# Motores.net
KiCad netlist of a schematic drawn in EasyEDA Pro
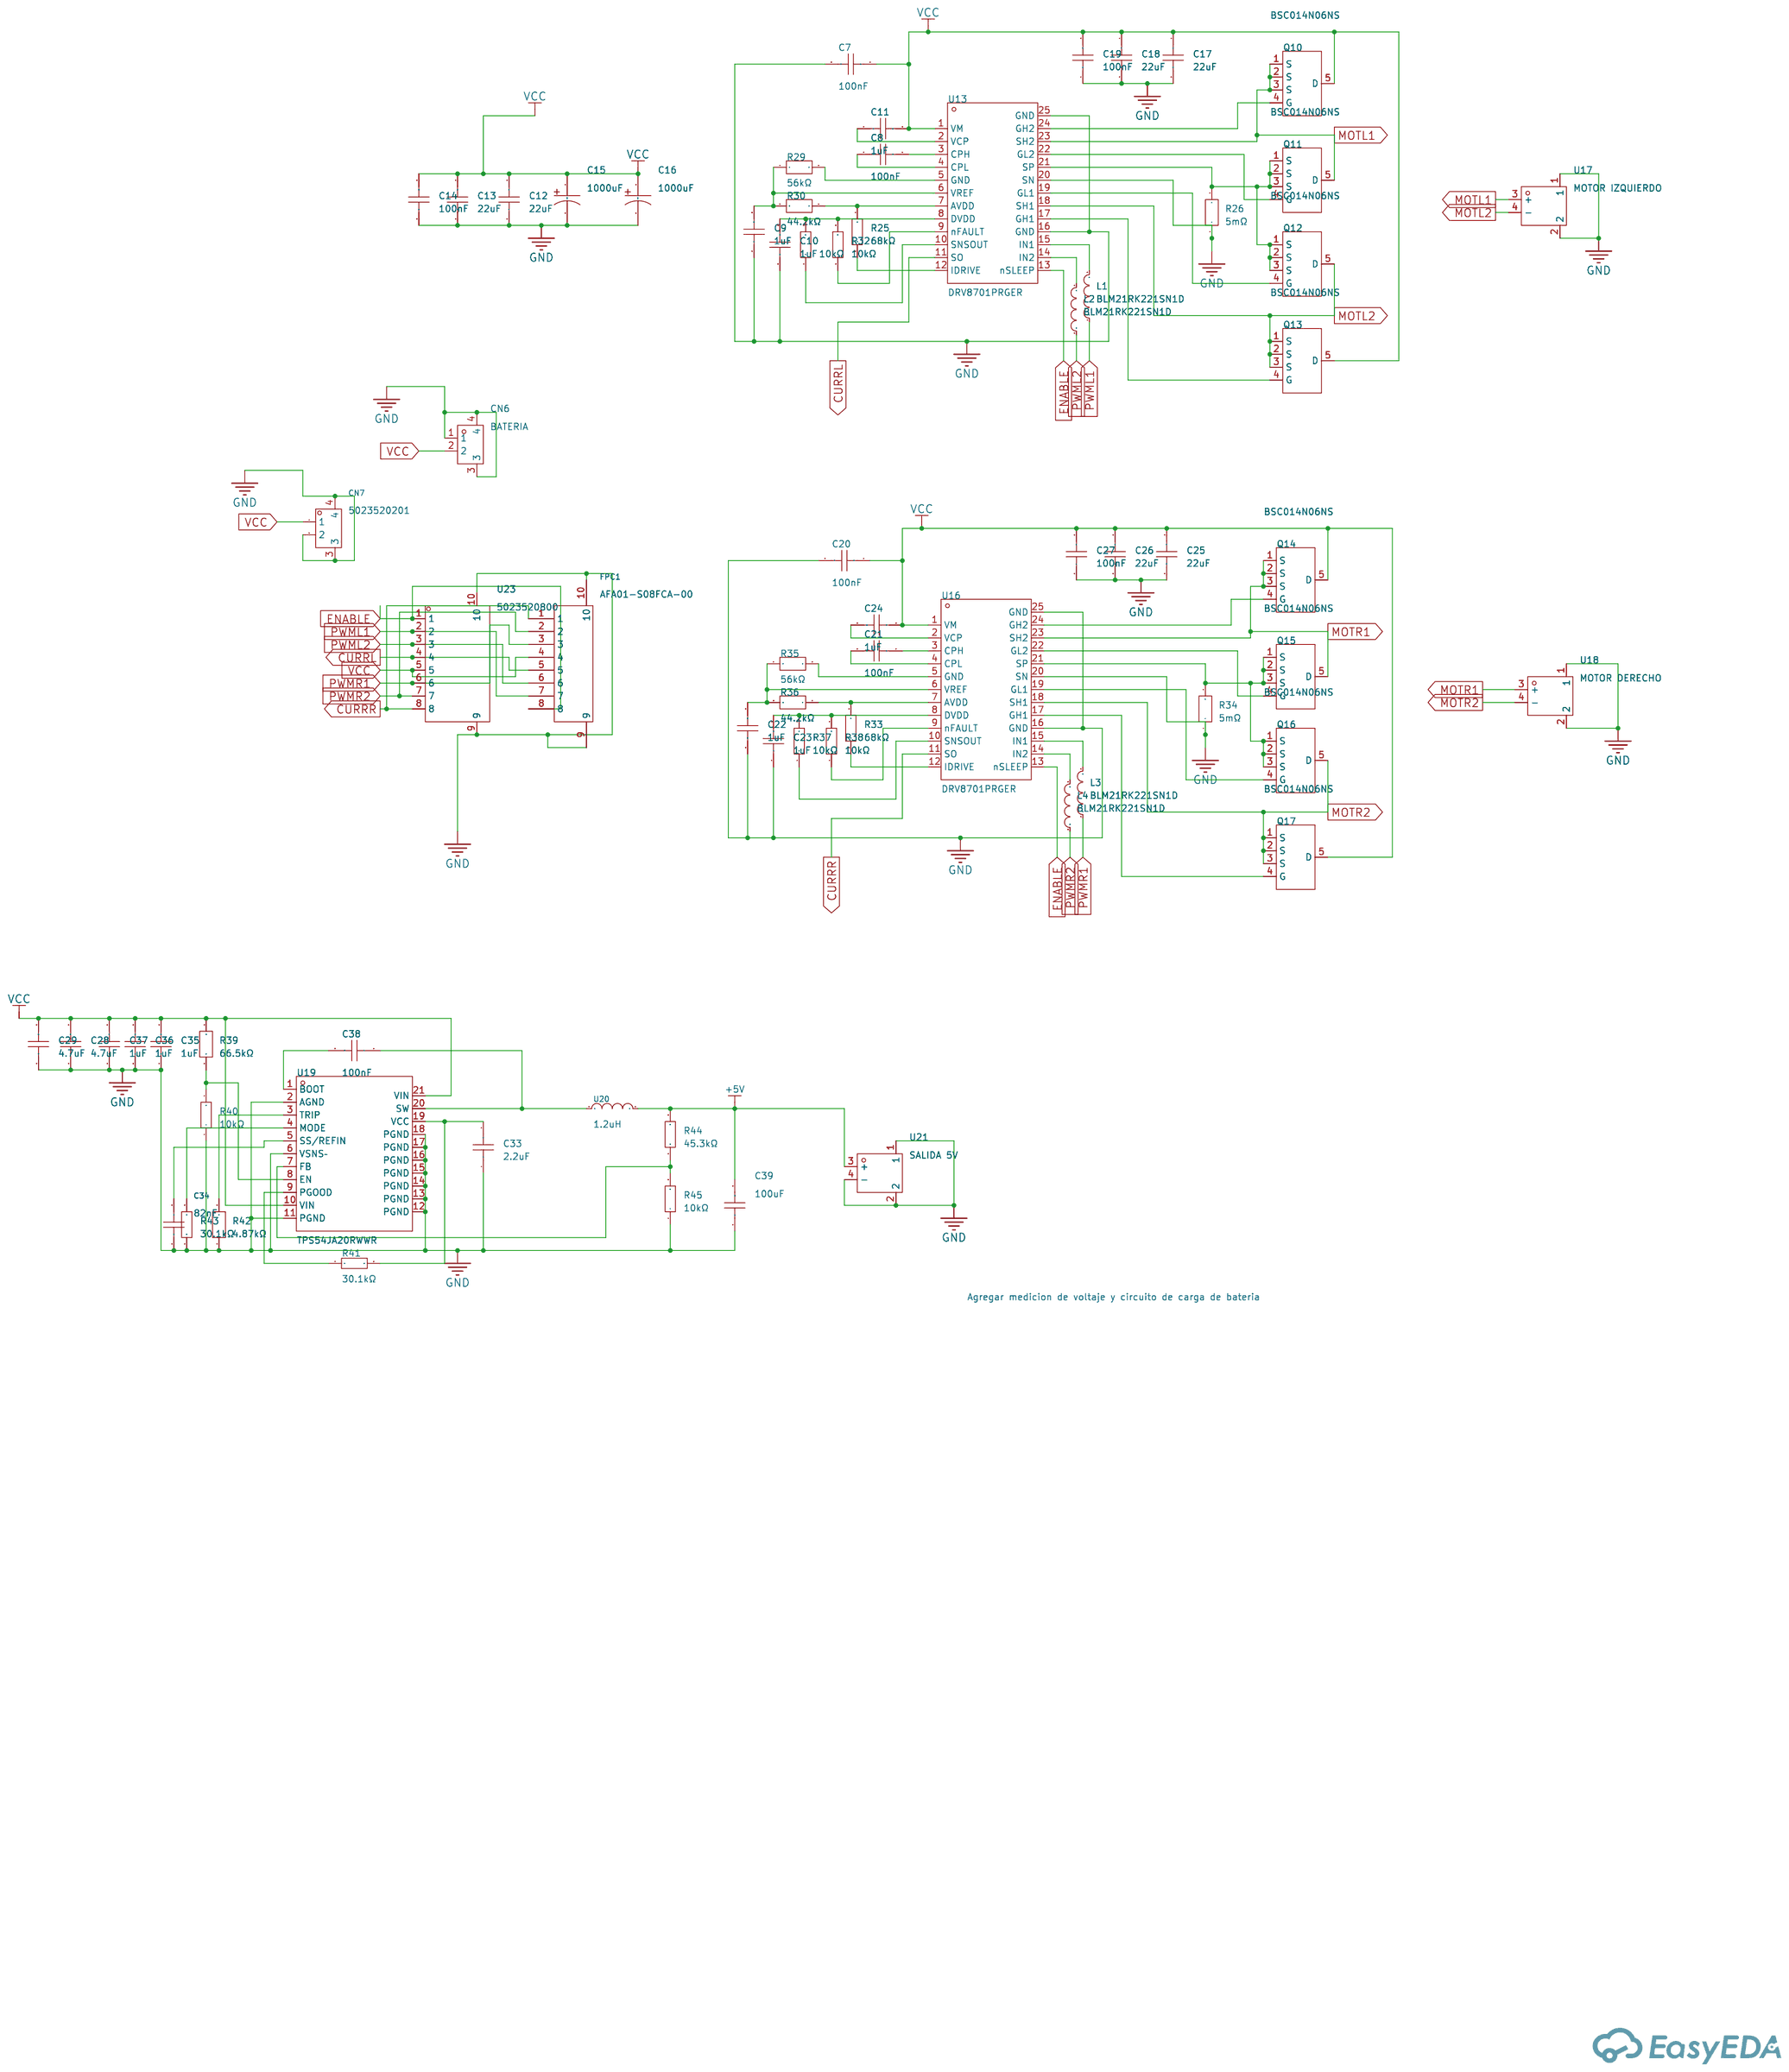
[diagram p0: schematic sheet]

(export (version "E")
  (design (tool "Eeschema 10.0.6"))
  (components
    (comp (ref "C7")
      (value "100nF")
      (footprint "easyedapro:C0805")
      (fields
        (field (name "Manufacturer Part") "CC0805JRX7R8BB104")
        (field (name "Manufacturer") "YAGEO(国巨)")
      )
      (libsource (lib "easyedapro") (part "CC0805JRX7R8BB104"))
    )
    (comp (ref "C8")
      (value "100nF")
      (footprint "easyedapro:C0805")
      (fields
        (field (name "Manufacturer Part") "CC0805JRX7R8BB104")
        (field (name "Manufacturer") "YAGEO(国巨)")
      )
      (libsource (lib "easyedapro") (part "CC0805JRX7R8BB104"))
    )
    (comp (ref "C9")
      (value "1uF")
      (footprint "easyedapro:C0805")
      (fields
        (field (name "Manufacturer Part") "CC0805JKX7R9BB105")
        (field (name "Manufacturer") "YAGEO(国巨)")
      )
      (libsource (lib "easyedapro") (part "CC0805JKX7R9BB105"))
    )
    (comp (ref "C10")
      (value "1uF")
      (footprint "easyedapro:C0805")
      (fields
        (field (name "Manufacturer Part") "CC0805JKX7R9BB105")
        (field (name "Manufacturer") "YAGEO(国巨)")
      )
      (libsource (lib "easyedapro") (part "CC0805JKX7R9BB105"))
    )
    (comp (ref "C11")
      (value "1uF")
      (footprint "easyedapro:C0805")
      (fields
        (field (name "Manufacturer Part") "CC0805JKX7R9BB105")
        (field (name "Manufacturer") "YAGEO(国巨)")
      )
      (libsource (lib "easyedapro") (part "CC0805JKX7R9BB105"))
    )
    (comp (ref "C12")
      (value "22uF")
      (footprint "easyedapro:C1210")
      (fields
        (field (name "Manufacturer Part") "GCM32ER71C226KE19L")
        (field (name "Manufacturer") "muRata(村田)")
      )
      (libsource (lib "easyedapro") (part "GCM32ER71C226KE19L"))
    )
    (comp (ref "C13")
      (value "22uF")
      (footprint "easyedapro:C1210")
      (fields
        (field (name "Manufacturer Part") "GCM32ER71C226KE19L")
        (field (name "Manufacturer") "muRata(村田)")
      )
      (libsource (lib "easyedapro") (part "GCM32ER71C226KE19L"))
    )
    (comp (ref "C14")
      (value "100nF")
      (footprint "easyedapro:C1206")
      (description "Capacitance:100nF Tolerance:±1% Tolerance:±1% Voltage Rating:50V Temperature Coefficient:C0G")
      (fields
        (field (name "Manufacturer Part") "GRM31C5C1H104FA01L")
        (field (name "Manufacturer") "muRata(村田)")
      )
      (libsource (lib "easyedapro") (part "GRM31C5C1H104FA01L"))
    )
    (comp (ref "C15")
      (value "1000uF")
      (footprint "easyedapro:CAP-SMD_BD10.0-L10.3-W10.3-FD")
      (fields (field (name "Manufacturer Part") "16SVPF1000M") (field (name "Manufacturer") "PANASONIC(松下)"))
      (libsource (lib "easyedapro") (part "16SVPF1000M"))
    )
    (comp (ref "C16")
      (value "1000uF")
      (footprint "easyedapro:CAP-SMD_BD10.0-L10.3-W10.3-FD")
      (fields (field (name "Manufacturer Part") "16SVPF1000M") (field (name "Manufacturer") "PANASONIC(松下)"))
      (libsource (lib "easyedapro") (part "16SVPF1000M"))
    )
    (comp (ref "C17")
      (value "22uF")
      (footprint "easyedapro:C1210")
      (fields
        (field (name "Manufacturer Part") "GCM32ER71C226KE19L")
        (field (name "Manufacturer") "muRata(村田)")
      )
      (libsource (lib "easyedapro") (part "GCM32ER71C226KE19L"))
    )
    (comp (ref "C18")
      (value "22uF")
      (footprint "easyedapro:C1210")
      (fields
        (field (name "Manufacturer Part") "GCM32ER71C226KE19L")
        (field (name "Manufacturer") "muRata(村田)")
      )
      (libsource (lib "easyedapro") (part "GCM32ER71C226KE19L"))
    )
    (comp (ref "C19")
      (value "100nF")
      (footprint "easyedapro:C1206")
      (description "Capacitance:100nF Tolerance:±1% Tolerance:±1% Voltage Rating:50V Temperature Coefficient:C0G")
      (fields
        (field (name "Manufacturer Part") "GRM31C5C1H104FA01L")
        (field (name "Manufacturer") "muRata(村田)")
      )
      (libsource (lib "easyedapro") (part "GRM31C5C1H104FA01L"))
    )
    (comp (ref "C20")
      (value "100nF")
      (footprint "easyedapro:C0805")
      (fields
        (field (name "Manufacturer Part") "CC0805JRX7R8BB104")
        (field (name "Manufacturer") "YAGEO(国巨)")
      )
      (libsource (lib "easyedapro") (part "CC0805JRX7R8BB104"))
    )
    (comp (ref "C21")
      (value "100nF")
      (footprint "easyedapro:C0805")
      (fields
        (field (name "Manufacturer Part") "CC0805JRX7R8BB104")
        (field (name "Manufacturer") "YAGEO(国巨)")
      )
      (libsource (lib "easyedapro") (part "CC0805JRX7R8BB104"))
    )
    (comp (ref "C22")
      (value "1uF")
      (footprint "easyedapro:C0805")
      (fields
        (field (name "Manufacturer Part") "CC0805JKX7R9BB105")
        (field (name "Manufacturer") "YAGEO(国巨)")
      )
      (libsource (lib "easyedapro") (part "CC0805JKX7R9BB105"))
    )
    (comp (ref "C23")
      (value "1uF")
      (footprint "easyedapro:C0805")
      (fields
        (field (name "Manufacturer Part") "CC0805JKX7R9BB105")
        (field (name "Manufacturer") "YAGEO(国巨)")
      )
      (libsource (lib "easyedapro") (part "CC0805JKX7R9BB105"))
    )
    (comp (ref "C24")
      (value "1uF")
      (footprint "easyedapro:C0805")
      (fields
        (field (name "Manufacturer Part") "CC0805JKX7R9BB105")
        (field (name "Manufacturer") "YAGEO(国巨)")
      )
      (libsource (lib "easyedapro") (part "CC0805JKX7R9BB105"))
    )
    (comp (ref "C25")
      (value "22uF")
      (footprint "easyedapro:C1210")
      (fields
        (field (name "Manufacturer Part") "GCM32ER71C226KE19L")
        (field (name "Manufacturer") "muRata(村田)")
      )
      (libsource (lib "easyedapro") (part "GCM32ER71C226KE19L"))
    )
    (comp (ref "C26")
      (value "22uF")
      (footprint "easyedapro:C1210")
      (fields
        (field (name "Manufacturer Part") "GCM32ER71C226KE19L")
        (field (name "Manufacturer") "muRata(村田)")
      )
      (libsource (lib "easyedapro") (part "GCM32ER71C226KE19L"))
    )
    (comp (ref "C27")
      (value "100nF")
      (footprint "easyedapro:C1206")
      (description "Capacitance:100nF Tolerance:±1% Tolerance:±1% Voltage Rating:50V Temperature Coefficient:C0G")
      (fields
        (field (name "Manufacturer Part") "GRM31C5C1H104FA01L")
        (field (name "Manufacturer") "muRata(村田)")
      )
      (libsource (lib "easyedapro") (part "GRM31C5C1H104FA01L"))
    )
    (comp (ref "C28")
      (value "4.7uF")
      (footprint "easyedapro:C0805")
      (fields
        (field (name "Manufacturer Part") "GRM21BZ71H475KE15L")
        (field (name "Manufacturer") "muRata(村田)")
      )
      (libsource (lib "easyedapro") (part "GRM21BZ71H475KE15L"))
    )
    (comp (ref "C29")
      (value "4.7uF")
      (footprint "easyedapro:C0805")
      (fields
        (field (name "Manufacturer Part") "GRM21BZ71H475KE15L")
        (field (name "Manufacturer") "muRata(村田)")
      )
      (libsource (lib "easyedapro") (part "GRM21BZ71H475KE15L"))
    )
    (comp (ref "C33")
      (value "2.2uF")
      (footprint "easyedapro:C0805")
      (description "Capacitance:2.2uF Tolerance:±10% Tolerance:±10% Voltage Rating:50V Temperature Coefficient:X5R")
      (fields
        (field (name "Manufacturer Part") "CS2012X5R225K500NRE")
        (field (name "Manufacturer") "SAMWHA(三和)")
      )
      (libsource (lib "easyedapro") (part "CS2012X5R225K500NRE"))
    )
    (comp (ref "C34")
      (value "82nF")
      (footprint "easyedapro:C0805")
      (fields (field (name "Manufacturer Part") "0805B823K500CT") (field (name "Manufacturer") "Walsin(华新科)"))
      (libsource (lib "easyedapro") (part "0805B823K500CT"))
    )
    (comp (ref "C35")
      (value "1uF")
      (footprint "easyedapro:C0805")
      (fields
        (field (name "Manufacturer Part") "CC0805JKX7R9BB105")
        (field (name "Manufacturer") "YAGEO(国巨)")
      )
      (libsource (lib "easyedapro") (part "CC0805JKX7R9BB105"))
    )
    (comp (ref "C36")
      (value "1uF")
      (footprint "easyedapro:C0805")
      (fields
        (field (name "Manufacturer Part") "CC0805JKX7R9BB105")
        (field (name "Manufacturer") "YAGEO(国巨)")
      )
      (libsource (lib "easyedapro") (part "CC0805JKX7R9BB105"))
    )
    (comp (ref "C37")
      (value "1uF")
      (footprint "easyedapro:C0805")
      (fields
        (field (name "Manufacturer Part") "CC0805JKX7R9BB105")
        (field (name "Manufacturer") "YAGEO(国巨)")
      )
      (libsource (lib "easyedapro") (part "CC0805JKX7R9BB105"))
    )
    (comp (ref "C38")
      (value "100nF")
      (footprint "easyedapro:C1206")
      (description "Capacitance:100nF Tolerance:±1% Tolerance:±1% Voltage Rating:50V Temperature Coefficient:C0G")
      (fields
        (field (name "Manufacturer Part") "GRM31C5C1H104FA01L")
        (field (name "Manufacturer") "muRata(村田)")
      )
      (libsource (lib "easyedapro") (part "GRM31C5C1H104FA01L"))
    )
    (comp (ref "C39")
      (value "100uF")
      (footprint "easyedapro:C1210")
      (description "Capacitance:100uF Tolerance:±20% Tolerance:±20% Voltage Rating:6.3V Temperature Coefficient:X6S")
      (fields (field (name "Manufacturer Part") "C3225X6S0J107MT000N") (field (name "Manufacturer") "TDK"))
      (libsource (lib "easyedapro") (part "C3225X6S0J107MT000N"))
    )
    (comp (ref "CN6")
      (value "BATERIA")
      (footprint "easyedapro:CONN-TH_XT90PW-M.G.Y")
      (fields (field (name "Manufacturer Part") "XT90PW-M.G.Y") (field (name "Manufacturer") "AMASS(艾迈斯)"))
      (libsource (lib "easyedapro") (part "XT90PW-M.G.Y"))
    )
    (comp (ref "CN7")
      (value "5023520201")
      (footprint "easyedapro:CONN-SMD_2P-P2.00_MOLEX_5023520201")
      (fields (field (name "Manufacturer") "MOLEX"))
      (libsource (lib "easyedapro") (part "5023520201"))
    )
    (comp (ref "FPC1")
      (value "AFA01-S08FCA-00")
      (footprint "easyedapro:FPC-SMD_8P-P1.00_FGS-XJ-H2.0")
      (fields (field (name "Manufacturer") "JS(钜硕电子)"))
      (libsource (lib "easyedapro") (part "AFA01-S08FCA-00"))
    )
    (comp (ref "L1")
      (value "BLM21RK221SN1D")
      (footprint "easyedapro:L0805")
      (fields (field (name "Manufacturer") "muRata(村田)"))
      (libsource (lib "easyedapro") (part "BLM21RK221SN1D"))
    )
    (comp (ref "L2")
      (value "BLM21RK221SN1D")
      (footprint "easyedapro:L0805")
      (fields (field (name "Manufacturer") "muRata(村田)"))
      (libsource (lib "easyedapro") (part "BLM21RK221SN1D"))
    )
    (comp (ref "L3")
      (value "BLM21RK221SN1D")
      (footprint "easyedapro:L0805")
      (fields (field (name "Manufacturer") "muRata(村田)"))
      (libsource (lib "easyedapro") (part "BLM21RK221SN1D"))
    )
    (comp (ref "L4")
      (value "BLM21RK221SN1D")
      (footprint "easyedapro:L0805")
      (fields (field (name "Manufacturer") "muRata(村田)"))
      (libsource (lib "easyedapro") (part "BLM21RK221SN1D"))
    )
    (comp (ref "Q10")
      (value "BSC014N06NS")
      (footprint "easyedapro:POWERVDFN-8_L6.2-W5.2-P1.27-LS6.0-BL")
      (fields (field (name "Manufacturer") "Infineon(英飞凌)"))
      (libsource (lib "easyedapro") (part "BSC014N06NS"))
    )
    (comp (ref "Q11")
      (value "BSC014N06NS")
      (footprint "easyedapro:POWERVDFN-8_L6.2-W5.2-P1.27-LS6.0-BL")
      (fields (field (name "Manufacturer") "Infineon(英飞凌)"))
      (libsource (lib "easyedapro") (part "BSC014N06NS"))
    )
    (comp (ref "Q12")
      (value "BSC014N06NS")
      (footprint "easyedapro:POWERVDFN-8_L6.2-W5.2-P1.27-LS6.0-BL")
      (fields (field (name "Manufacturer") "Infineon(英飞凌)"))
      (libsource (lib "easyedapro") (part "BSC014N06NS"))
    )
    (comp (ref "Q13")
      (value "BSC014N06NS")
      (footprint "easyedapro:POWERVDFN-8_L6.2-W5.2-P1.27-LS6.0-BL")
      (fields (field (name "Manufacturer") "Infineon(英飞凌)"))
      (libsource (lib "easyedapro") (part "BSC014N06NS"))
    )
    (comp (ref "Q14")
      (value "BSC014N06NS")
      (footprint "easyedapro:POWERVDFN-8_L6.2-W5.2-P1.27-LS6.0-BL")
      (fields (field (name "Manufacturer") "Infineon(英飞凌)"))
      (libsource (lib "easyedapro") (part "BSC014N06NS"))
    )
    (comp (ref "Q15")
      (value "BSC014N06NS")
      (footprint "easyedapro:POWERVDFN-8_L6.2-W5.2-P1.27-LS6.0-BL")
      (fields (field (name "Manufacturer") "Infineon(英飞凌)"))
      (libsource (lib "easyedapro") (part "BSC014N06NS"))
    )
    (comp (ref "Q16")
      (value "BSC014N06NS")
      (footprint "easyedapro:POWERVDFN-8_L6.2-W5.2-P1.27-LS6.0-BL")
      (fields (field (name "Manufacturer") "Infineon(英飞凌)"))
      (libsource (lib "easyedapro") (part "BSC014N06NS"))
    )
    (comp (ref "Q17")
      (value "BSC014N06NS")
      (footprint "easyedapro:POWERVDFN-8_L6.2-W5.2-P1.27-LS6.0-BL")
      (fields (field (name "Manufacturer") "Infineon(英飞凌)"))
      (libsource (lib "easyedapro") (part "BSC014N06NS"))
    )
    (comp (ref "R25")
      (value "68kΩ")
      (footprint "easyedapro:R0805")
      (fields (field (name "Manufacturer Part") "RC0805FR-0768KL") (field (name "Manufacturer") "YAGEO(国巨)"))
      (libsource (lib "easyedapro") (part "RC0805FR-0768KL"))
    )
    (comp (ref "R26")
      (value "5mΩ")
      (footprint "easyedapro:RES-SMD_L11.6-W7.0_WSR5")
      (fields (field (name "Manufacturer Part") "WSR55L000FEA") (field (name "Manufacturer") "VISHAY(威世)"))
      (libsource (lib "easyedapro") (part "WSR55L000FEA"))
    )
    (comp (ref "R29")
      (value "56kΩ")
      (footprint "easyedapro:R0603")
      (fields (field (name "Manufacturer Part") "RT0603BRD0756KL") (field (name "Manufacturer") "YAGEO(国巨)"))
      (libsource (lib "easyedapro") (part "RT0603BRD0756KL"))
    )
    (comp (ref "R30")
      (value "44.2kΩ")
      (footprint "easyedapro:R0603")
      (fields (field (name "Manufacturer Part") "RT0603BRD0744K2L") (field (name "Manufacturer") "YAGEO(国巨)"))
      (libsource (lib "easyedapro") (part "RT0603BRD0744K2L"))
    )
    (comp (ref "R31")
      (value "10kΩ")
      (footprint "easyedapro:R0805")
      (fields
        (field (name "Manufacturer Part") "0805W8F1002T5E")
        (field (name "Manufacturer") "UNI-ROYAL(厚声)")
      )
      (libsource (lib "easyedapro") (part "0805W8F1002T5E"))
    )
    (comp (ref "R32")
      (value "10kΩ")
      (footprint "easyedapro:R0805")
      (fields
        (field (name "Manufacturer Part") "0805W8F1002T5E")
        (field (name "Manufacturer") "UNI-ROYAL(厚声)")
      )
      (libsource (lib "easyedapro") (part "0805W8F1002T5E"))
    )
    (comp (ref "R33")
      (value "68kΩ")
      (footprint "easyedapro:R0805")
      (fields (field (name "Manufacturer Part") "RC0805FR-0768KL") (field (name "Manufacturer") "YAGEO(国巨)"))
      (libsource (lib "easyedapro") (part "RC0805FR-0768KL"))
    )
    (comp (ref "R34")
      (value "5mΩ")
      (footprint "easyedapro:RES-SMD_L11.6-W7.0_WSR5")
      (fields (field (name "Manufacturer Part") "WSR55L000FEA") (field (name "Manufacturer") "VISHAY(威世)"))
      (libsource (lib "easyedapro") (part "WSR55L000FEA"))
    )
    (comp (ref "R35")
      (value "56kΩ")
      (footprint "easyedapro:R0603")
      (fields (field (name "Manufacturer Part") "RT0603BRD0756KL") (field (name "Manufacturer") "YAGEO(国巨)"))
      (libsource (lib "easyedapro") (part "RT0603BRD0756KL"))
    )
    (comp (ref "R36")
      (value "44.2kΩ")
      (footprint "easyedapro:R0603")
      (fields (field (name "Manufacturer Part") "RT0603BRD0744K2L") (field (name "Manufacturer") "YAGEO(国巨)"))
      (libsource (lib "easyedapro") (part "RT0603BRD0744K2L"))
    )
    (comp (ref "R37")
      (value "10kΩ")
      (footprint "easyedapro:R0805")
      (fields
        (field (name "Manufacturer Part") "0805W8F1002T5E")
        (field (name "Manufacturer") "UNI-ROYAL(厚声)")
      )
      (libsource (lib "easyedapro") (part "0805W8F1002T5E"))
    )
    (comp (ref "R38")
      (value "10kΩ")
      (footprint "easyedapro:R0805")
      (fields
        (field (name "Manufacturer Part") "0805W8F1002T5E")
        (field (name "Manufacturer") "UNI-ROYAL(厚声)")
      )
      (libsource (lib "easyedapro") (part "0805W8F1002T5E"))
    )
    (comp (ref "R39")
      (value "66.5kΩ")
      (footprint "easyedapro:R0805")
      (fields (field (name "Manufacturer Part") "FRC0805F6652TS") (field (name "Manufacturer") "FOJAN(富捷)"))
      (libsource (lib "easyedapro") (part "FRC0805F6652TS"))
    )
    (comp (ref "R40")
      (value "10kΩ")
      (footprint "easyedapro:R0805")
      (fields
        (field (name "Manufacturer Part") "0805W8F1002T5E")
        (field (name "Manufacturer") "UNI-ROYAL(厚声)")
      )
      (libsource (lib "easyedapro") (part "0805W8F1002T5E"))
    )
    (comp (ref "R41")
      (value "30.1kΩ")
      (footprint "easyedapro:R0805")
      (fields (field (name "Manufacturer Part") "RS-05K3012FT") (field (name "Manufacturer") "FH(风华)"))
      (libsource (lib "easyedapro") (part "RS-05K3012FT"))
    )
    (comp (ref "R42")
      (value "4.87kΩ")
      (footprint "easyedapro:R0805")
      (fields (field (name "Manufacturer Part") "FRC0805F4871TS") (field (name "Manufacturer") "FOJAN(富捷)"))
      (libsource (lib "easyedapro") (part "FRC0805F4871TS"))
    )
    (comp (ref "R43")
      (value "30.1kΩ")
      (footprint "easyedapro:R0805")
      (fields (field (name "Manufacturer Part") "RS-05K3012FT") (field (name "Manufacturer") "FH(风华)"))
      (libsource (lib "easyedapro") (part "RS-05K3012FT"))
    )
    (comp (ref "R44")
      (value "45.3kΩ")
      (footprint "easyedapro:R0805")
      (fields (field (name "Manufacturer Part") "RS-05K4532FT") (field (name "Manufacturer") "FH(风华)"))
      (libsource (lib "easyedapro") (part "RS-05K4532FT"))
    )
    (comp (ref "R45")
      (value "10kΩ")
      (footprint "easyedapro:R0805")
      (fields
        (field (name "Manufacturer Part") "0805W8F1002T5E")
        (field (name "Manufacturer") "UNI-ROYAL(厚声)")
      )
      (libsource (lib "easyedapro") (part "0805W8F1002T5E"))
    )
    (comp (ref "U13")
      (value "DRV8701PRGER")
      (footprint "easyedapro:VQFN-24_L4.0-W4.0-P0.50-BL-EP2.8")
      (fields (field (name "Manufacturer") "TI(德州仪器)"))
      (libsource (lib "easyedapro") (part "DRV8701PRGER"))
    )
    (comp (ref "U16")
      (value "DRV8701PRGER")
      (footprint "easyedapro:VQFN-24_L4.0-W4.0-P0.50-BL-EP2.8")
      (fields (field (name "Manufacturer") "TI(德州仪器)"))
      (libsource (lib "easyedapro") (part "DRV8701PRGER"))
    )
    (comp (ref "U17")
      (value "MOTOR IZQUIERDO")
      (footprint "easyedapro:TH_2P-XT60PW-F")
      (fields (field (name "Manufacturer Part") "XT60PW-F") (field (name "Manufacturer") "AMASS(艾迈斯)"))
      (libsource (lib "easyedapro") (part "XT60PW-F_C428722"))
    )
    (comp (ref "U18")
      (value "MOTOR DERECHO")
      (footprint "easyedapro:TH_2P-XT60PW-F")
      (fields (field (name "Manufacturer Part") "XT60PW-F") (field (name "Manufacturer") "AMASS(艾迈斯)"))
      (libsource (lib "easyedapro") (part "XT60PW-F_C428722"))
    )
    (comp (ref "U19")
      (value "TPS54JA20RWWR")
      (footprint "easyedapro:TQFN-21_L4.0-W3.0-P0.40-TL_MPQ8633BGLE-Z")
      (fields (field (name "Manufacturer") "TI(德州仪器)"))
      (libsource (lib "easyedapro") (part "TPS54JA20RWWR"))
    )
    (comp (ref "U20")
      (value "1.2uH")
      (footprint "easyedapro:IND-SMD_L7.0-W6.6_0630CDMCCDS")
      (fields
        (field (name "Manufacturer Part") "0630CDMCDDS-1R2MC")
        (field (name "Manufacturer") "Sumida(胜美达)")
      )
      (libsource (lib "easyedapro") (part "0630CDMCDDS-1R2MC"))
    )
    (comp (ref "U21")
      (value "SALIDA 5V")
      (footprint "easyedapro:TH_2P-XT60PW-F")
      (fields (field (name "Manufacturer Part") "XT60PW-F") (field (name "Manufacturer") "AMASS(艾迈斯)"))
      (libsource (lib "easyedapro") (part "XT60PW-F_C428722"))
    )
    (comp (ref "U23")
      (value "5023520800")
      (footprint "easyedapro:CONN-SMD_5023520800")
      (fields (field (name "Manufacturer") "MOLEX"))
      (libsource (lib "easyedapro") (part "5023520800"))
    )
  )
  (nets
    (net (code "1") (name "+5V") (class "Default")
      (node (ref "C39") (pin "2") (pinfunction "2_2") (pintype "unspecified"))
      (node (ref "R44") (pin "2") (pinfunction "2_2") (pintype "unspecified"))
      (node (ref "U20") (pin "2") (pinfunction "2_2") (pintype "input"))
      (node (ref "U21") (pin "3") (pinfunction "+_3") (pintype "unspecified"))
    )
    (net (code "2") (name "CURRL") (class "Default")
      (node (ref "FPC1") (pin "5") (pinfunction "5_5") (pintype "input"))
      (node (ref "U13") (pin "11") (pinfunction "SO_11") (pintype "unspecified"))
      (node (ref "U23") (pin "4") (pinfunction "4_4") (pintype "unspecified"))
    )
    (net (code "3") (name "CURRR") (class "Default")
      (node (ref "FPC1") (pin "1") (pinfunction "1_1") (pintype "input"))
      (node (ref "U16") (pin "11") (pinfunction "SO_11") (pintype "unspecified"))
      (node (ref "U23") (pin "8") (pinfunction "8_8") (pintype "unspecified"))
    )
    (net (code "4") (name "ENABLE") (class "Default")
      (node (ref "FPC1") (pin "8") (pinfunction "8_8") (pintype "input"))
      (node (ref "U13") (pin "13") (pinfunction "nSLEEP_13") (pintype "unspecified"))
      (node (ref "U16") (pin "13") (pinfunction "nSLEEP_13") (pintype "unspecified"))
      (node (ref "U23") (pin "1") (pinfunction "1_1") (pintype "unspecified"))
    )
    (net (code "5") (name "GND") (class "Default")
      (node (ref "C10") (pin "1") (pinfunction "1_1") (pintype "unspecified"))
      (node (ref "C12") (pin "2") (pinfunction "2_2") (pintype "unspecified"))
      (node (ref "C13") (pin "2") (pinfunction "2_2") (pintype "unspecified"))
      (node (ref "C14") (pin "1") (pinfunction "1_1") (pintype "unspecified"))
      (node (ref "C15") (pin "2") (pinfunction "2_2") (pintype "unspecified"))
      (node (ref "C16") (pin "2") (pinfunction "2_2") (pintype "unspecified"))
      (node (ref "C17") (pin "2") (pinfunction "2_2") (pintype "unspecified"))
      (node (ref "C18") (pin "2") (pinfunction "2_2") (pintype "unspecified"))
      (node (ref "C19") (pin "1") (pinfunction "1_1") (pintype "unspecified"))
      (node (ref "C20") (pin "2") (pinfunction "2_2") (pintype "unspecified"))
      (node (ref "C22") (pin "1") (pinfunction "1_1") (pintype "unspecified"))
      (node (ref "C23") (pin "1") (pinfunction "1_1") (pintype "unspecified"))
      (node (ref "C25") (pin "2") (pinfunction "2_2") (pintype "unspecified"))
      (node (ref "C26") (pin "2") (pinfunction "2_2") (pintype "unspecified"))
      (node (ref "C27") (pin "1") (pinfunction "1_1") (pintype "unspecified"))
      (node (ref "C28") (pin "1") (pinfunction "1_1") (pintype "unspecified"))
      (node (ref "C29") (pin "1") (pinfunction "1_1") (pintype "unspecified"))
      (node (ref "C33") (pin "1") (pinfunction "1_1") (pintype "unspecified"))
      (node (ref "C34") (pin "1") (pinfunction "1_1") (pintype "input"))
      (node (ref "C35") (pin "1") (pinfunction "1_1") (pintype "unspecified"))
      (node (ref "C36") (pin "1") (pinfunction "1_1") (pintype "unspecified"))
      (node (ref "C37") (pin "1") (pinfunction "1_1") (pintype "unspecified"))
      (node (ref "C39") (pin "1") (pinfunction "1_1") (pintype "unspecified"))
      (node (ref "C7") (pin "2") (pinfunction "2_2") (pintype "unspecified"))
      (node (ref "C9") (pin "1") (pinfunction "1_1") (pintype "unspecified"))
      (node (ref "CN6") (pin "1") (pinfunction "1_1") (pintype "unspecified"))
      (node (ref "CN6") (pin "3") (pinfunction "3_3") (pintype "unspecified"))
      (node (ref "CN6") (pin "4") (pinfunction "4_4") (pintype "unspecified"))
      (node (ref "CN7") (pin "2") (pinfunction "2_2") (pintype "input"))
      (node (ref "CN7") (pin "3") (pinfunction "3_3") (pintype "input"))
      (node (ref "CN7") (pin "4") (pinfunction "4_4") (pintype "input"))
      (node (ref "FPC1") (pin "10") (pinfunction "10_10") (pintype "input"))
      (node (ref "FPC1") (pin "9") (pinfunction "9_9") (pintype "input"))
      (node (ref "R26") (pin "1") (pinfunction "1_1") (pintype "unspecified"))
      (node (ref "R34") (pin "1") (pinfunction "1_1") (pintype "unspecified"))
      (node (ref "R40") (pin "1") (pinfunction "1_1") (pintype "input"))
      (node (ref "R42") (pin "1") (pinfunction "1_1") (pintype "unspecified"))
      (node (ref "R43") (pin "1") (pinfunction "1_1") (pintype "unspecified"))
      (node (ref "R45") (pin "1") (pinfunction "1_1") (pintype "input"))
      (node (ref "U13") (pin "16") (pinfunction "GND_16") (pintype "unspecified"))
      (node (ref "U13") (pin "20") (pinfunction "SN_20") (pintype "unspecified"))
      (node (ref "U13") (pin "25") (pinfunction "GND_25") (pintype "unspecified"))
      (node (ref "U16") (pin "16") (pinfunction "GND_16") (pintype "unspecified"))
      (node (ref "U16") (pin "20") (pinfunction "SN_20") (pintype "unspecified"))
      (node (ref "U16") (pin "25") (pinfunction "GND_25") (pintype "unspecified"))
      (node (ref "U17") (pin "1") (pinfunction "1_1") (pintype "unspecified"))
      (node (ref "U17") (pin "2") (pinfunction "2_2") (pintype "unspecified"))
      (node (ref "U18") (pin "1") (pinfunction "1_1") (pintype "unspecified"))
      (node (ref "U18") (pin "2") (pinfunction "2_2") (pintype "unspecified"))
      (node (ref "U19") (pin "11") (pinfunction "PGND_11") (pintype "unspecified"))
      (node (ref "U19") (pin "12") (pinfunction "PGND_12") (pintype "unspecified"))
      (node (ref "U19") (pin "13") (pinfunction "PGND_13") (pintype "unspecified"))
      (node (ref "U19") (pin "14") (pinfunction "PGND_14") (pintype "unspecified"))
      (node (ref "U19") (pin "15") (pinfunction "PGND_15") (pintype "unspecified"))
      (node (ref "U19") (pin "16") (pinfunction "PGND_16") (pintype "unspecified"))
      (node (ref "U19") (pin "17") (pinfunction "PGND_17") (pintype "unspecified"))
      (node (ref "U19") (pin "18") (pinfunction "PGND_18") (pintype "unspecified"))
      (node (ref "U19") (pin "2") (pinfunction "AGND_2") (pintype "unspecified"))
      (node (ref "U19") (pin "6") (pinfunction "VSNS–_6") (pintype "unspecified"))
      (node (ref "U21") (pin "1") (pinfunction "1_1") (pintype "unspecified"))
      (node (ref "U21") (pin "2") (pinfunction "2_2") (pintype "unspecified"))
      (node (ref "U21") (pin "4") (pinfunction "-_4") (pintype "unspecified"))
      (node (ref "U23") (pin "10") (pinfunction "10_10") (pintype "unspecified"))
      (node (ref "U23") (pin "9") (pinfunction "9_9") (pintype "unspecified"))
    )
    (net (code "6") (name "MOTL1") (class "Default")
      (node (ref "Q10") (pin "1") (pinfunction "S_1") (pintype "unspecified"))
      (node (ref "Q10") (pin "2") (pinfunction "S_2") (pintype "unspecified"))
      (node (ref "Q10") (pin "3") (pinfunction "S_3") (pintype "unspecified"))
      (node (ref "Q11") (pin "5") (pinfunction "D_5") (pintype "unspecified"))
      (node (ref "U13") (pin "23") (pinfunction "SH2_23") (pintype "unspecified"))
      (node (ref "U17") (pin "3") (pinfunction "+_3") (pintype "unspecified"))
    )
    (net (code "7") (name "MOTL2") (class "Default")
      (node (ref "Q12") (pin "5") (pinfunction "D_5") (pintype "unspecified"))
      (node (ref "Q13") (pin "1") (pinfunction "S_1") (pintype "unspecified"))
      (node (ref "Q13") (pin "2") (pinfunction "S_2") (pintype "unspecified"))
      (node (ref "Q13") (pin "3") (pinfunction "S_3") (pintype "unspecified"))
      (node (ref "U13") (pin "18") (pinfunction "SH1_18") (pintype "unspecified"))
      (node (ref "U17") (pin "4") (pinfunction "-_4") (pintype "unspecified"))
    )
    (net (code "8") (name "MOTR1") (class "Default")
      (node (ref "Q14") (pin "1") (pinfunction "S_1") (pintype "unspecified"))
      (node (ref "Q14") (pin "2") (pinfunction "S_2") (pintype "unspecified"))
      (node (ref "Q14") (pin "3") (pinfunction "S_3") (pintype "unspecified"))
      (node (ref "Q15") (pin "5") (pinfunction "D_5") (pintype "unspecified"))
      (node (ref "U16") (pin "23") (pinfunction "SH2_23") (pintype "unspecified"))
      (node (ref "U18") (pin "3") (pinfunction "+_3") (pintype "unspecified"))
    )
    (net (code "9") (name "MOTR2") (class "Default")
      (node (ref "Q16") (pin "5") (pinfunction "D_5") (pintype "unspecified"))
      (node (ref "Q17") (pin "1") (pinfunction "S_1") (pintype "unspecified"))
      (node (ref "Q17") (pin "2") (pinfunction "S_2") (pintype "unspecified"))
      (node (ref "Q17") (pin "3") (pinfunction "S_3") (pintype "unspecified"))
      (node (ref "U16") (pin "18") (pinfunction "SH1_18") (pintype "unspecified"))
      (node (ref "U18") (pin "4") (pinfunction "-_4") (pintype "unspecified"))
    )
    (net (code "10") (name "Net-(Q10-G)") (class "Default")
      (node (ref "Q10") (pin "4") (pinfunction "G_4") (pintype "unspecified"))
      (node (ref "U13") (pin "24") (pinfunction "GH2_24") (pintype "unspecified"))
    )
    (net (code "11") (name "Net-(Q11-G)") (class "Default")
      (node (ref "Q11") (pin "4") (pinfunction "G_4") (pintype "unspecified"))
      (node (ref "U13") (pin "22") (pinfunction "GL2_22") (pintype "unspecified"))
    )
    (net (code "12") (name "Net-(Q12-G)") (class "Default")
      (node (ref "Q12") (pin "4") (pinfunction "G_4") (pintype "unspecified"))
      (node (ref "U13") (pin "19") (pinfunction "GL1_19") (pintype "unspecified"))
    )
    (net (code "13") (name "Net-(Q13-G)") (class "Default")
      (node (ref "Q13") (pin "4") (pinfunction "G_4") (pintype "unspecified"))
      (node (ref "U13") (pin "17") (pinfunction "GH1_17") (pintype "unspecified"))
    )
    (net (code "14") (name "Net-(Q14-G)") (class "Default")
      (node (ref "Q14") (pin "4") (pinfunction "G_4") (pintype "unspecified"))
      (node (ref "U16") (pin "24") (pinfunction "GH2_24") (pintype "unspecified"))
    )
    (net (code "15") (name "Net-(Q15-G)") (class "Default")
      (node (ref "Q15") (pin "4") (pinfunction "G_4") (pintype "unspecified"))
      (node (ref "U16") (pin "22") (pinfunction "GL2_22") (pintype "unspecified"))
    )
    (net (code "16") (name "Net-(Q16-G)") (class "Default")
      (node (ref "Q16") (pin "4") (pinfunction "G_4") (pintype "unspecified"))
      (node (ref "U16") (pin "19") (pinfunction "GL1_19") (pintype "unspecified"))
    )
    (net (code "17") (name "Net-(Q17-G)") (class "Default")
      (node (ref "Q17") (pin "4") (pinfunction "G_4") (pintype "unspecified"))
      (node (ref "U16") (pin "17") (pinfunction "GH1_17") (pintype "unspecified"))
    )
    (net (code "18") (name "Net-(R29-Pad2)") (class "Default")
      (node (ref "R29") (pin "2") (pinfunction "2_2") (pintype "unspecified"))
      (node (ref "U13") (pin "5") (pinfunction "GND_5") (pintype "unspecified"))
    )
    (net (code "19") (name "Net-(R35-Pad2)") (class "Default")
      (node (ref "R35") (pin "2") (pinfunction "2_2") (pintype "unspecified"))
      (node (ref "U16") (pin "5") (pinfunction "GND_5") (pintype "unspecified"))
    )
    (net (code "20") (name "Net-(U13-AVDD)") (class "Default")
      (node (ref "R25") (pin "1") (pinfunction "1_1") (pintype "input"))
      (node (ref "R30") (pin "1") (pinfunction "1_1") (pintype "unspecified"))
      (node (ref "U13") (pin "7") (pinfunction "AVDD_7") (pintype "unspecified"))
    )
    (net (code "21") (name "Net-(U13-CPH)") (class "Default")
      (node (ref "C8") (pin "1") (pinfunction "1_1") (pintype "unspecified"))
      (node (ref "U13") (pin "3") (pinfunction "CPH_3") (pintype "unspecified"))
    )
    (net (code "22") (name "Net-(U13-CPL)") (class "Default")
      (node (ref "C8") (pin "2") (pinfunction "2_2") (pintype "unspecified"))
      (node (ref "U13") (pin "4") (pinfunction "CPL_4") (pintype "unspecified"))
    )
    (net (code "23") (name "Net-(U13-DVDD)") (class "Default")
      (node (ref "C10") (pin "2") (pinfunction "2_2") (pintype "unspecified"))
      (node (ref "R31") (pin "2") (pinfunction "2_2") (pintype "input"))
      (node (ref "R32") (pin "2") (pinfunction "2_2") (pintype "input"))
      (node (ref "U13") (pin "8") (pinfunction "DVDD_8") (pintype "unspecified"))
    )
    (net (code "24") (name "Net-(U13-IDRIVE)") (class "Default")
      (node (ref "R25") (pin "2") (pinfunction "2_2") (pintype "input"))
      (node (ref "U13") (pin "12") (pinfunction "IDRIVE_12") (pintype "unspecified"))
    )
    (net (code "25") (name "Net-(U13-IN1)") (class "Default")
      (node (ref "L1") (pin "2") (pinfunction "2_2") (pintype "unspecified"))
      (node (ref "U13") (pin "15") (pinfunction "IN1_15") (pintype "unspecified"))
    )
    (net (code "26") (name "Net-(U13-IN2)") (class "Default")
      (node (ref "L2") (pin "2") (pinfunction "2_2") (pintype "unspecified"))
      (node (ref "U13") (pin "14") (pinfunction "IN2_14") (pintype "unspecified"))
    )
    (net (code "27") (name "Net-(U13-SNSOUT)") (class "Default")
      (node (ref "R31") (pin "1") (pinfunction "1_1") (pintype "input"))
      (node (ref "U13") (pin "10") (pinfunction "SNSOUT_10") (pintype "unspecified"))
    )
    (net (code "28") (name "Net-(U13-SP)") (class "Default")
      (node (ref "Q11") (pin "1") (pinfunction "S_1") (pintype "unspecified"))
      (node (ref "Q11") (pin "2") (pinfunction "S_2") (pintype "unspecified"))
      (node (ref "Q11") (pin "3") (pinfunction "S_3") (pintype "unspecified"))
      (node (ref "Q12") (pin "1") (pinfunction "S_1") (pintype "unspecified"))
      (node (ref "Q12") (pin "2") (pinfunction "S_2") (pintype "unspecified"))
      (node (ref "Q12") (pin "3") (pinfunction "S_3") (pintype "unspecified"))
      (node (ref "R26") (pin "2") (pinfunction "2_2") (pintype "unspecified"))
      (node (ref "U13") (pin "21") (pinfunction "SP_21") (pintype "unspecified"))
    )
    (net (code "29") (name "Net-(U13-VCP)") (class "Default")
      (node (ref "C11") (pin "1") (pinfunction "1_1") (pintype "unspecified"))
      (node (ref "U13") (pin "2") (pinfunction "VCP_2") (pintype "unspecified"))
    )
    (net (code "30") (name "Net-(U13-VREF)") (class "Default")
      (node (ref "C9") (pin "2") (pinfunction "2_2") (pintype "unspecified"))
      (node (ref "R29") (pin "1") (pinfunction "1_1") (pintype "unspecified"))
      (node (ref "R30") (pin "2") (pinfunction "2_2") (pintype "unspecified"))
      (node (ref "U13") (pin "6") (pinfunction "VREF_6") (pintype "unspecified"))
    )
    (net (code "31") (name "Net-(U13-nFAULT)") (class "Default")
      (node (ref "R32") (pin "1") (pinfunction "1_1") (pintype "input"))
      (node (ref "U13") (pin "9") (pinfunction "nFAULT_9") (pintype "unspecified"))
    )
    (net (code "32") (name "Net-(U16-AVDD)") (class "Default")
      (node (ref "R33") (pin "1") (pinfunction "1_1") (pintype "input"))
      (node (ref "R36") (pin "1") (pinfunction "1_1") (pintype "unspecified"))
      (node (ref "U16") (pin "7") (pinfunction "AVDD_7") (pintype "unspecified"))
    )
    (net (code "33") (name "Net-(U16-CPH)") (class "Default")
      (node (ref "C21") (pin "1") (pinfunction "1_1") (pintype "unspecified"))
      (node (ref "U16") (pin "3") (pinfunction "CPH_3") (pintype "unspecified"))
    )
    (net (code "34") (name "Net-(U16-CPL)") (class "Default")
      (node (ref "C21") (pin "2") (pinfunction "2_2") (pintype "unspecified"))
      (node (ref "U16") (pin "4") (pinfunction "CPL_4") (pintype "unspecified"))
    )
    (net (code "35") (name "Net-(U16-DVDD)") (class "Default")
      (node (ref "C23") (pin "2") (pinfunction "2_2") (pintype "unspecified"))
      (node (ref "R37") (pin "2") (pinfunction "2_2") (pintype "input"))
      (node (ref "R38") (pin "2") (pinfunction "2_2") (pintype "input"))
      (node (ref "U16") (pin "8") (pinfunction "DVDD_8") (pintype "unspecified"))
    )
    (net (code "36") (name "Net-(U16-IDRIVE)") (class "Default")
      (node (ref "R33") (pin "2") (pinfunction "2_2") (pintype "input"))
      (node (ref "U16") (pin "12") (pinfunction "IDRIVE_12") (pintype "unspecified"))
    )
    (net (code "37") (name "Net-(U16-IN1)") (class "Default")
      (node (ref "L3") (pin "2") (pinfunction "2_2") (pintype "unspecified"))
      (node (ref "U16") (pin "15") (pinfunction "IN1_15") (pintype "unspecified"))
    )
    (net (code "38") (name "Net-(U16-IN2)") (class "Default")
      (node (ref "L4") (pin "2") (pinfunction "2_2") (pintype "unspecified"))
      (node (ref "U16") (pin "14") (pinfunction "IN2_14") (pintype "unspecified"))
    )
    (net (code "39") (name "Net-(U16-SNSOUT)") (class "Default")
      (node (ref "R37") (pin "1") (pinfunction "1_1") (pintype "input"))
      (node (ref "U16") (pin "10") (pinfunction "SNSOUT_10") (pintype "unspecified"))
    )
    (net (code "40") (name "Net-(U16-SP)") (class "Default")
      (node (ref "Q15") (pin "1") (pinfunction "S_1") (pintype "unspecified"))
      (node (ref "Q15") (pin "2") (pinfunction "S_2") (pintype "unspecified"))
      (node (ref "Q15") (pin "3") (pinfunction "S_3") (pintype "unspecified"))
      (node (ref "Q16") (pin "1") (pinfunction "S_1") (pintype "unspecified"))
      (node (ref "Q16") (pin "2") (pinfunction "S_2") (pintype "unspecified"))
      (node (ref "Q16") (pin "3") (pinfunction "S_3") (pintype "unspecified"))
      (node (ref "R34") (pin "2") (pinfunction "2_2") (pintype "unspecified"))
      (node (ref "U16") (pin "21") (pinfunction "SP_21") (pintype "unspecified"))
    )
    (net (code "41") (name "Net-(U16-VCP)") (class "Default")
      (node (ref "C24") (pin "1") (pinfunction "1_1") (pintype "unspecified"))
      (node (ref "U16") (pin "2") (pinfunction "VCP_2") (pintype "unspecified"))
    )
    (net (code "42") (name "Net-(U16-VREF)") (class "Default")
      (node (ref "C22") (pin "2") (pinfunction "2_2") (pintype "unspecified"))
      (node (ref "R35") (pin "1") (pinfunction "1_1") (pintype "unspecified"))
      (node (ref "R36") (pin "2") (pinfunction "2_2") (pintype "unspecified"))
      (node (ref "U16") (pin "6") (pinfunction "VREF_6") (pintype "unspecified"))
    )
    (net (code "43") (name "Net-(U16-nFAULT)") (class "Default")
      (node (ref "R38") (pin "1") (pinfunction "1_1") (pintype "input"))
      (node (ref "U16") (pin "9") (pinfunction "nFAULT_9") (pintype "unspecified"))
    )
    (net (code "44") (name "Net-(U19-BOOT)") (class "Default")
      (node (ref "C38") (pin "2") (pinfunction "2_2") (pintype "unspecified"))
      (node (ref "U19") (pin "1") (pinfunction "BOOT_1") (pintype "unspecified"))
    )
    (net (code "45") (name "Net-(U19-EN)") (class "Default")
      (node (ref "R39") (pin "1") (pinfunction "1_1") (pintype "unspecified"))
      (node (ref "R40") (pin "2") (pinfunction "2_2") (pintype "input"))
      (node (ref "U19") (pin "8") (pinfunction "EN_8") (pintype "unspecified"))
    )
    (net (code "46") (name "Net-(U19-FB)") (class "Default")
      (node (ref "R44") (pin "1") (pinfunction "1_1") (pintype "unspecified"))
      (node (ref "R45") (pin "2") (pinfunction "2_2") (pintype "input"))
      (node (ref "U19") (pin "7") (pinfunction "FB_7") (pintype "unspecified"))
    )
    (net (code "47") (name "Net-(U19-MODE)") (class "Default")
      (node (ref "R43") (pin "2") (pinfunction "2_2") (pintype "unspecified"))
      (node (ref "U19") (pin "4") (pinfunction "MODE_4") (pintype "unspecified"))
    )
    (net (code "48") (name "Net-(U19-PGOOD)") (class "Default")
      (node (ref "R41") (pin "1") (pinfunction "1_1") (pintype "unspecified"))
      (node (ref "U19") (pin "9") (pinfunction "PGOOD_9") (pintype "unspecified"))
    )
    (net (code "49") (name "Net-(U19-SS{slash}REFIN)") (class "Default")
      (node (ref "C34") (pin "2") (pinfunction "2_2") (pintype "input"))
      (node (ref "U19") (pin "5") (pinfunction "SS/REFIN_5") (pintype "unspecified"))
    )
    (net (code "50") (name "Net-(U19-SW)") (class "Default")
      (node (ref "C38") (pin "1") (pinfunction "1_1") (pintype "unspecified"))
      (node (ref "U19") (pin "20") (pinfunction "SW_20") (pintype "unspecified"))
      (node (ref "U20") (pin "1") (pinfunction "1_1") (pintype "input"))
    )
    (net (code "51") (name "Net-(U19-TRIP)") (class "Default")
      (node (ref "R42") (pin "2") (pinfunction "2_2") (pintype "unspecified"))
      (node (ref "U19") (pin "3") (pinfunction "TRIP_3") (pintype "unspecified"))
    )
    (net (code "52") (name "Net-(U19-VCC)") (class "Default")
      (node (ref "C33") (pin "2") (pinfunction "2_2") (pintype "unspecified"))
      (node (ref "R41") (pin "2") (pinfunction "2_2") (pintype "unspecified"))
      (node (ref "U19") (pin "19") (pinfunction "VCC_19") (pintype "unspecified"))
    )
    (net (code "53") (name "PWML1") (class "Default")
      (node (ref "FPC1") (pin "7") (pinfunction "7_7") (pintype "input"))
      (node (ref "L1") (pin "1") (pinfunction "1_1") (pintype "unspecified"))
      (node (ref "U23") (pin "2") (pinfunction "2_2") (pintype "unspecified"))
    )
    (net (code "54") (name "PWML2") (class "Default")
      (node (ref "FPC1") (pin "6") (pinfunction "6_6") (pintype "input"))
      (node (ref "L2") (pin "1") (pinfunction "1_1") (pintype "unspecified"))
      (node (ref "U23") (pin "3") (pinfunction "3_3") (pintype "unspecified"))
    )
    (net (code "55") (name "PWMR1") (class "Default")
      (node (ref "FPC1") (pin "3") (pinfunction "3_3") (pintype "input"))
      (node (ref "L3") (pin "1") (pinfunction "1_1") (pintype "unspecified"))
      (node (ref "U23") (pin "6") (pinfunction "6_6") (pintype "unspecified"))
    )
    (net (code "56") (name "PWMR2") (class "Default")
      (node (ref "FPC1") (pin "2") (pinfunction "2_2") (pintype "input"))
      (node (ref "L4") (pin "1") (pinfunction "1_1") (pintype "unspecified"))
      (node (ref "U23") (pin "7") (pinfunction "7_7") (pintype "unspecified"))
    )
    (net (code "57") (name "VCC") (class "Default")
      (node (ref "C11") (pin "2") (pinfunction "2_2") (pintype "unspecified"))
      (node (ref "C12") (pin "1") (pinfunction "1_1") (pintype "unspecified"))
      (node (ref "C13") (pin "1") (pinfunction "1_1") (pintype "unspecified"))
      (node (ref "C14") (pin "2") (pinfunction "2_2") (pintype "unspecified"))
      (node (ref "C15") (pin "1") (pinfunction "1_1") (pintype "unspecified"))
      (node (ref "C16") (pin "1") (pinfunction "1_1") (pintype "unspecified"))
      (node (ref "C17") (pin "1") (pinfunction "1_1") (pintype "unspecified"))
      (node (ref "C18") (pin "1") (pinfunction "1_1") (pintype "unspecified"))
      (node (ref "C19") (pin "2") (pinfunction "2_2") (pintype "unspecified"))
      (node (ref "C20") (pin "1") (pinfunction "1_1") (pintype "unspecified"))
      (node (ref "C24") (pin "2") (pinfunction "2_2") (pintype "unspecified"))
      (node (ref "C25") (pin "1") (pinfunction "1_1") (pintype "unspecified"))
      (node (ref "C26") (pin "1") (pinfunction "1_1") (pintype "unspecified"))
      (node (ref "C27") (pin "2") (pinfunction "2_2") (pintype "unspecified"))
      (node (ref "C28") (pin "2") (pinfunction "2_2") (pintype "unspecified"))
      (node (ref "C29") (pin "2") (pinfunction "2_2") (pintype "unspecified"))
      (node (ref "C35") (pin "2") (pinfunction "2_2") (pintype "unspecified"))
      (node (ref "C36") (pin "2") (pinfunction "2_2") (pintype "unspecified"))
      (node (ref "C37") (pin "2") (pinfunction "2_2") (pintype "unspecified"))
      (node (ref "C7") (pin "1") (pinfunction "1_1") (pintype "unspecified"))
      (node (ref "CN6") (pin "2") (pinfunction "2_2") (pintype "unspecified"))
      (node (ref "CN7") (pin "1") (pinfunction "1_1") (pintype "input"))
      (node (ref "FPC1") (pin "4") (pinfunction "4_4") (pintype "input"))
      (node (ref "Q10") (pin "5") (pinfunction "D_5") (pintype "unspecified"))
      (node (ref "Q13") (pin "5") (pinfunction "D_5") (pintype "unspecified"))
      (node (ref "Q14") (pin "5") (pinfunction "D_5") (pintype "unspecified"))
      (node (ref "Q17") (pin "5") (pinfunction "D_5") (pintype "unspecified"))
      (node (ref "R39") (pin "2") (pinfunction "2_2") (pintype "unspecified"))
      (node (ref "U13") (pin "1") (pinfunction "VM_1") (pintype "unspecified"))
      (node (ref "U16") (pin "1") (pinfunction "VM_1") (pintype "unspecified"))
      (node (ref "U19") (pin "10") (pinfunction "VIN_10") (pintype "unspecified"))
      (node (ref "U19") (pin "21") (pinfunction "VIN_21") (pintype "unspecified"))
      (node (ref "U23") (pin "5") (pinfunction "5_5") (pintype "unspecified"))
    )
  )
)
